# Mod_Intan_v1.net
KiCad netlist of a schematic drawn in Altium Designer
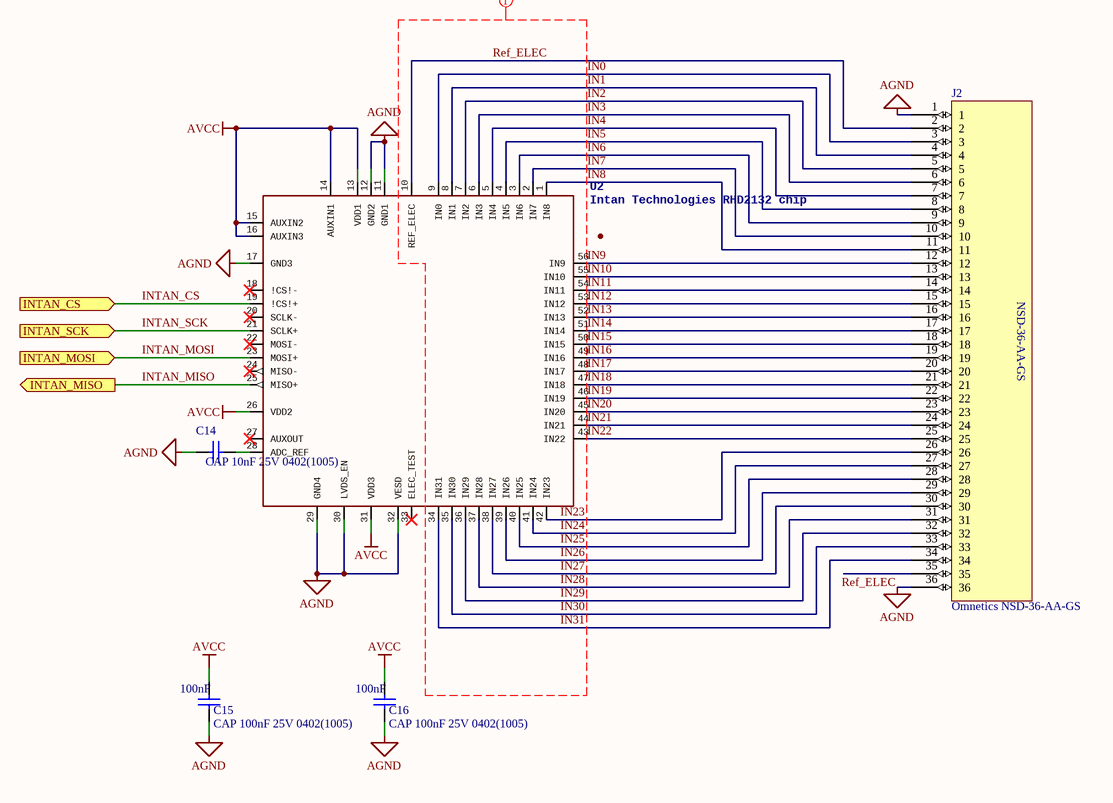
[diagram p0: Mod_Intan_v1.SchDoc]

(export (version "E")
  (design (tool "Eeschema 10.0.6"))
  (components
    (comp (ref "C14")
      (value "CAP 10nF 25V 0402(1005)")
      (footprint "CAPC0402(1005)60_L")
      (description "CAP 10nF 25V ±5% 0402 (1005 Metric) Thickness 0.6mm SMD")
      (fields (field (name "TOLERANCE") "±5%"))
      (libsource (lib "Altium Content Vault") (part "CAP"))
    )
    (comp (ref "C15")
      (value "CAP 100nF 25V 0402(1005)")
      (footprint "CAPC0402(1005)60_L")
      (description "CAP 100nF 25V ±10% 0402 (1005 Metric) Thickness 0.6mm SMD")
      (fields (field (name "ALTIUM_VALUE") "100nF") (field (name "TOLERANCE") "±10%"))
      (libsource (lib "Altium Content Vault") (part "CAP"))
    )
    (comp (ref "C16")
      (value "CAP 100nF 25V 0402(1005)")
      (footprint "CAPC0402(1005)60_L")
      (description "CAP 100nF 25V ±10% 0402 (1005 Metric) Thickness 0.6mm SMD")
      (fields (field (name "ALTIUM_VALUE") "100nF") (field (name "TOLERANCE") "±10%"))
      (libsource (lib "Altium Content Vault") (part "CAP"))
    )
    (comp (ref "J2")
      (value "Omnetics NSD-36-AA-GS")
      (footprint "NSD-36-AA-GS")
      (description "NSD-36-AA-GS")
      (fields (field (name "PART NUMBER") "A79025-001"))
      (libsource (lib "USBridge") (part "Omnetics NSD-36-AA-GS"))
    )
    (comp (ref "U2")
      (value "Intan Technologies RHD2132 chip")
      (footprint "QFN56_large")
      (libsource (lib "RHD2000") (part "RHD2132_QFN"))
    )
  )
  (nets
    (net (code "1") (name "/IN0") (class "Default")
      (node (ref "J2") (pin "3") (pinfunction "3_3") (pintype "bidirectional"))
      (node (ref "U2") (pin "9") (pinfunction "IN0_9") (pintype "passive"))
    )
    (net (code "2") (name "/IN1") (class "Default")
      (node (ref "J2") (pin "4") (pinfunction "4_4") (pintype "bidirectional"))
      (node (ref "U2") (pin "8") (pinfunction "IN1_8") (pintype "passive"))
    )
    (net (code "3") (name "/IN2") (class "Default")
      (node (ref "J2") (pin "5") (pinfunction "5_5") (pintype "bidirectional"))
      (node (ref "U2") (pin "7") (pinfunction "IN2_7") (pintype "passive"))
    )
    (net (code "4") (name "/IN3") (class "Default")
      (node (ref "J2") (pin "6") (pinfunction "6_6") (pintype "bidirectional"))
      (node (ref "U2") (pin "6") (pinfunction "IN3_6") (pintype "passive"))
    )
    (net (code "5") (name "/IN4") (class "Default")
      (node (ref "J2") (pin "7") (pinfunction "7_7") (pintype "bidirectional"))
      (node (ref "U2") (pin "5") (pinfunction "IN4_5") (pintype "passive"))
    )
    (net (code "6") (name "/IN5") (class "Default")
      (node (ref "J2") (pin "8") (pinfunction "8_8") (pintype "bidirectional"))
      (node (ref "U2") (pin "4") (pinfunction "IN5_4") (pintype "passive"))
    )
    (net (code "7") (name "/IN6") (class "Default")
      (node (ref "J2") (pin "9") (pinfunction "9_9") (pintype "bidirectional"))
      (node (ref "U2") (pin "3") (pinfunction "IN6_3") (pintype "passive"))
    )
    (net (code "8") (name "/IN7") (class "Default")
      (node (ref "J2") (pin "10") (pinfunction "10_10") (pintype "bidirectional"))
      (node (ref "U2") (pin "2") (pinfunction "IN7_2") (pintype "passive"))
    )
    (net (code "9") (name "/IN8") (class "Default")
      (node (ref "J2") (pin "11") (pinfunction "11_11") (pintype "bidirectional"))
      (node (ref "U2") (pin "1") (pinfunction "IN8_1") (pintype "passive"))
    )
    (net (code "10") (name "/IN9") (class "Default")
      (node (ref "J2") (pin "12") (pinfunction "12_12") (pintype "bidirectional"))
      (node (ref "U2") (pin "56") (pinfunction "IN9_56") (pintype "passive"))
    )
    (net (code "11") (name "/IN10") (class "Default")
      (node (ref "J2") (pin "13") (pinfunction "13_13") (pintype "bidirectional"))
      (node (ref "U2") (pin "55") (pinfunction "IN10_55") (pintype "passive"))
    )
    (net (code "12") (name "/IN11") (class "Default")
      (node (ref "J2") (pin "14") (pinfunction "14_14") (pintype "bidirectional"))
      (node (ref "U2") (pin "54") (pinfunction "IN11_54") (pintype "passive"))
    )
    (net (code "13") (name "/IN12") (class "Default")
      (node (ref "J2") (pin "15") (pinfunction "15_15") (pintype "bidirectional"))
      (node (ref "U2") (pin "53") (pinfunction "IN12_53") (pintype "passive"))
    )
    (net (code "14") (name "/IN13") (class "Default")
      (node (ref "J2") (pin "16") (pinfunction "16_16") (pintype "bidirectional"))
      (node (ref "U2") (pin "52") (pinfunction "IN13_52") (pintype "passive"))
    )
    (net (code "15") (name "/IN14") (class "Default")
      (node (ref "J2") (pin "17") (pinfunction "17_17") (pintype "bidirectional"))
      (node (ref "U2") (pin "51") (pinfunction "IN14_51") (pintype "passive"))
    )
    (net (code "16") (name "/IN15") (class "Default")
      (node (ref "J2") (pin "18") (pinfunction "18_18") (pintype "bidirectional"))
      (node (ref "U2") (pin "50") (pinfunction "IN15_50") (pintype "passive"))
    )
    (net (code "17") (name "/IN16") (class "Default")
      (node (ref "J2") (pin "19") (pinfunction "19_19") (pintype "bidirectional"))
      (node (ref "U2") (pin "49") (pinfunction "IN16_49") (pintype "passive"))
    )
    (net (code "18") (name "/IN17") (class "Default")
      (node (ref "J2") (pin "20") (pinfunction "20_20") (pintype "bidirectional"))
      (node (ref "U2") (pin "48") (pinfunction "IN17_48") (pintype "passive"))
    )
    (net (code "19") (name "/IN18") (class "Default")
      (node (ref "J2") (pin "21") (pinfunction "21_21") (pintype "bidirectional"))
      (node (ref "U2") (pin "47") (pinfunction "IN18_47") (pintype "passive"))
    )
    (net (code "20") (name "/IN19") (class "Default")
      (node (ref "J2") (pin "22") (pinfunction "22_22") (pintype "bidirectional"))
      (node (ref "U2") (pin "46") (pinfunction "IN19_46") (pintype "passive"))
    )
    (net (code "21") (name "/IN20") (class "Default")
      (node (ref "J2") (pin "23") (pinfunction "23_23") (pintype "bidirectional"))
      (node (ref "U2") (pin "45") (pinfunction "IN20_45") (pintype "passive"))
    )
    (net (code "22") (name "/IN21") (class "Default")
      (node (ref "J2") (pin "24") (pinfunction "24_24") (pintype "bidirectional"))
      (node (ref "U2") (pin "44") (pinfunction "IN21_44") (pintype "passive"))
    )
    (net (code "23") (name "/IN22") (class "Default")
      (node (ref "J2") (pin "25") (pinfunction "25_25") (pintype "bidirectional"))
      (node (ref "U2") (pin "43") (pinfunction "IN22_43") (pintype "passive"))
    )
    (net (code "24") (name "/IN23") (class "Default")
      (node (ref "J2") (pin "26") (pinfunction "26_26") (pintype "bidirectional"))
      (node (ref "U2") (pin "42") (pinfunction "IN23_42") (pintype "passive"))
    )
    (net (code "25") (name "/IN24") (class "Default")
      (node (ref "J2") (pin "27") (pinfunction "27_27") (pintype "bidirectional"))
      (node (ref "U2") (pin "41") (pinfunction "IN24_41") (pintype "passive"))
    )
    (net (code "26") (name "/IN25") (class "Default")
      (node (ref "J2") (pin "28") (pinfunction "28_28") (pintype "bidirectional"))
      (node (ref "U2") (pin "40") (pinfunction "IN25_40") (pintype "passive"))
    )
    (net (code "27") (name "/IN26") (class "Default")
      (node (ref "J2") (pin "29") (pinfunction "29_29") (pintype "bidirectional"))
      (node (ref "U2") (pin "39") (pinfunction "IN26_39") (pintype "passive"))
    )
    (net (code "28") (name "/IN27") (class "Default")
      (node (ref "J2") (pin "30") (pinfunction "30_30") (pintype "bidirectional"))
      (node (ref "U2") (pin "38") (pinfunction "IN27_38") (pintype "passive"))
    )
    (net (code "29") (name "/IN28") (class "Default")
      (node (ref "J2") (pin "31") (pinfunction "31_31") (pintype "bidirectional"))
      (node (ref "U2") (pin "37") (pinfunction "IN28_37") (pintype "passive"))
    )
    (net (code "30") (name "/IN29") (class "Default")
      (node (ref "J2") (pin "32") (pinfunction "32_32") (pintype "bidirectional"))
      (node (ref "U2") (pin "36") (pinfunction "IN29_36") (pintype "passive"))
    )
    (net (code "31") (name "/IN30") (class "Default")
      (node (ref "J2") (pin "33") (pinfunction "33_33") (pintype "bidirectional"))
      (node (ref "U2") (pin "35") (pinfunction "IN30_35") (pintype "passive"))
    )
    (net (code "32") (name "/IN31") (class "Default")
      (node (ref "J2") (pin "34") (pinfunction "34_34") (pintype "bidirectional"))
      (node (ref "U2") (pin "34") (pinfunction "IN31_34") (pintype "passive"))
    )
    (net (code "33") (name "/INTAN_CS") (class "Default")
      (node (ref "U2") (pin "19") (pinfunction "!CS!+_19") (pintype "passive"))
    )
    (net (code "34") (name "/INTAN_MISO") (class "Default")
      (node (ref "U2") (pin "25") (pinfunction "MISO+_25") (pintype "output"))
    )
    (net (code "35") (name "/INTAN_MOSI") (class "Default")
      (node (ref "U2") (pin "23") (pinfunction "MOSI+_23") (pintype "passive"))
    )
    (net (code "36") (name "/INTAN_SCK") (class "Default")
      (node (ref "U2") (pin "21") (pinfunction "SCLK+_21") (pintype "passive"))
    )
    (net (code "37") (name "/Ref_ELEC") (class "Default")
      (node (ref "J2") (pin "2") (pinfunction "2_2") (pintype "bidirectional"))
      (node (ref "J2") (pin "35") (pinfunction "35_35") (pintype "bidirectional"))
      (node (ref "U2") (pin "10") (pinfunction "REF_ELEC_10") (pintype "passive"))
    )
    (net (code "38") (name "AGND") (class "Default")
      (node (ref "C14") (pin "1") (pinfunction "1_1") (pintype "passive"))
      (node (ref "C15") (pin "1") (pinfunction "1_1") (pintype "passive"))
      (node (ref "C16") (pin "1") (pinfunction "1_1") (pintype "passive"))
      (node (ref "J2") (pin "1") (pinfunction "1_1") (pintype "bidirectional"))
      (node (ref "J2") (pin "36") (pinfunction "36_36") (pintype "bidirectional"))
      (node (ref "U2") (pin "11") (pinfunction "GND1_11") (pintype "power_in"))
      (node (ref "U2") (pin "12") (pinfunction "GND2_12") (pintype "power_in"))
      (node (ref "U2") (pin "17") (pinfunction "GND3_17") (pintype "power_in"))
      (node (ref "U2") (pin "29") (pinfunction "GND4_29") (pintype "power_in"))
      (node (ref "U2") (pin "30") (pinfunction "LVDS_EN_30") (pintype "passive"))
      (node (ref "U2") (pin "32") (pinfunction "VESD_32") (pintype "power_in"))
    )
    (net (code "39") (name "AVCC") (class "Default")
      (node (ref "C15") (pin "2") (pinfunction "2_2") (pintype "passive"))
      (node (ref "C16") (pin "2") (pinfunction "2_2") (pintype "passive"))
      (node (ref "U2") (pin "13") (pinfunction "VDD1_13") (pintype "power_in"))
      (node (ref "U2") (pin "14") (pinfunction "AUXIN1_14") (pintype "passive"))
      (node (ref "U2") (pin "15") (pinfunction "AUXIN2_15") (pintype "passive"))
      (node (ref "U2") (pin "16") (pinfunction "AUXIN3_16") (pintype "passive"))
      (node (ref "U2") (pin "26") (pinfunction "VDD2_26") (pintype "power_in"))
      (node (ref "U2") (pin "31") (pinfunction "VDD3_31") (pintype "power_in"))
    )
    (net (code "40") (name "Net-(U2-ADC_REF)") (class "Default")
      (node (ref "C14") (pin "2") (pinfunction "2_2") (pintype "passive"))
      (node (ref "U2") (pin "28") (pinfunction "ADC_REF_28") (pintype "passive"))
    )
    (net (code "41") (name "unconnected-(U2-!CS!--Pad18)") (class "Default")
      (node (ref "U2") (pin "18") (pinfunction "!CS!-_18") (pintype "passive+no_connect"))
    )
    (net (code "42") (name "unconnected-(U2-AUXOUT-Pad27)") (class "Default")
      (node (ref "U2") (pin "27") (pinfunction "AUXOUT_27") (pintype "tri_state+no_connect"))
    )
    (net (code "43") (name "unconnected-(U2-ELEC_TEST-Pad33)") (class "Default")
      (node (ref "U2") (pin "33") (pinfunction "ELEC_TEST_33") (pintype "passive+no_connect"))
    )
    (net (code "44") (name "unconnected-(U2-MISO--Pad24)") (class "Default")
      (node (ref "U2") (pin "24") (pinfunction "MISO-_24") (pintype "output+no_connect"))
    )
    (net (code "45") (name "unconnected-(U2-MOSI--Pad22)") (class "Default")
      (node (ref "U2") (pin "22") (pinfunction "MOSI-_22") (pintype "passive+no_connect"))
    )
    (net (code "46") (name "unconnected-(U2-SCLK--Pad20)") (class "Default")
      (node (ref "U2") (pin "20") (pinfunction "SCLK-_20") (pintype "passive+no_connect"))
    )
  )
)
